# VentilationSystem_Rele.net
KiCad netlist of a schematic drawn in EAGLE
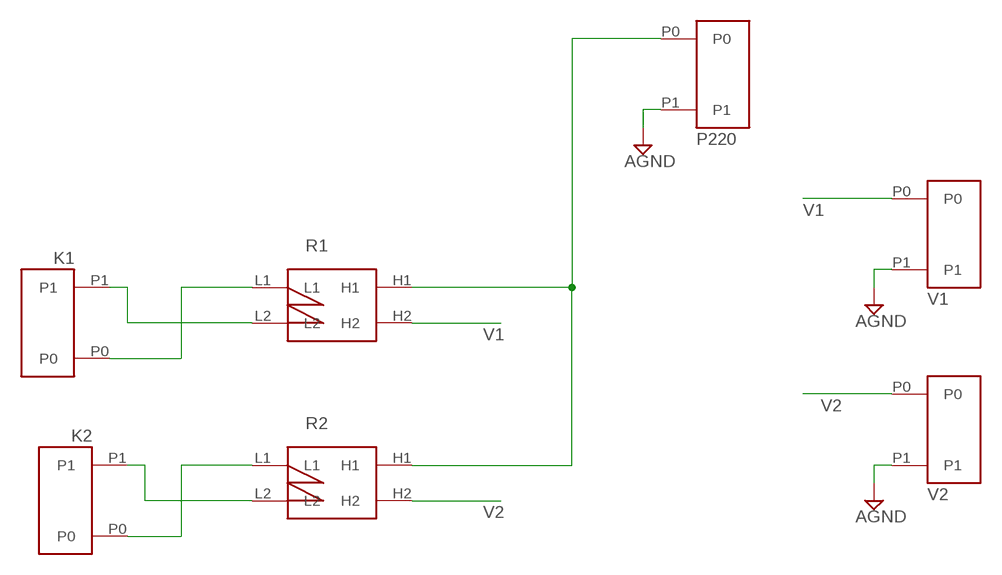
[diagram p0: schematic, sheet 1]

(export (version "E")
  (design (tool "Eeschema 10.0.6"))
  (components
    (comp (ref "K1")
      (value "RAIL_2")
      (footprint "eagle-import:RAIL_2")
      (libsource (lib "eagle-import") (part "RAIL_2"))
    )
    (comp (ref "K2")
      (value "RAIL_2")
      (footprint "eagle-import:RAIL_2")
      (libsource (lib "eagle-import") (part "RAIL_2"))
    )
    (comp (ref "P220")
      (value "RAIL_2")
      (footprint "eagle-import:RAIL_2")
      (libsource (lib "eagle-import") (part "RAIL_2"))
    )
    (comp (ref "R1")
      (value "NPR-RELE")
      (footprint "eagle-import:NPR-RELE")
      (libsource (lib "eagle-import") (part "NPR-RELE"))
    )
    (comp (ref "R2")
      (value "NPR-RELE")
      (footprint "eagle-import:NPR-RELE")
      (libsource (lib "eagle-import") (part "NPR-RELE"))
    )
    (comp (ref "V1")
      (value "RAIL_2")
      (footprint "eagle-import:RAIL_2")
      (libsource (lib "eagle-import") (part "RAIL_2"))
    )
    (comp (ref "V2")
      (value "RAIL_2")
      (footprint "eagle-import:RAIL_2")
      (libsource (lib "eagle-import") (part "RAIL_2"))
    )
  )
  (nets
    (net (code "1") (name "/V1") (class "Default")
      (node (ref "R1") (pin "H2") (pinfunction "H2_H2") (pintype "bidirectional"))
      (node (ref "V1") (pin "P0") (pinfunction "P0_P0") (pintype "bidirectional"))
    )
    (net (code "2") (name "/V2") (class "Default")
      (node (ref "R2") (pin "H2") (pinfunction "H2_H2") (pintype "bidirectional"))
      (node (ref "V2") (pin "P0") (pinfunction "P0_P0") (pintype "bidirectional"))
    )
    (net (code "3") (name "AGND") (class "Default")
      (node (ref "P220") (pin "P1") (pinfunction "P1_P1") (pintype "bidirectional"))
      (node (ref "V1") (pin "P1") (pinfunction "P1_P1") (pintype "bidirectional"))
      (node (ref "V2") (pin "P1") (pinfunction "P1_P1") (pintype "bidirectional"))
    )
    (net (code "4") (name "Net-(K1-PadP0)") (class "Default")
      (node (ref "K1") (pin "P0") (pinfunction "P0_P0") (pintype "bidirectional"))
      (node (ref "R1") (pin "L1") (pinfunction "L1_L1") (pintype "bidirectional"))
    )
    (net (code "5") (name "Net-(K1-PadP1)") (class "Default")
      (node (ref "K1") (pin "P1") (pinfunction "P1_P1") (pintype "bidirectional"))
      (node (ref "R1") (pin "L2") (pinfunction "L2_L2") (pintype "bidirectional"))
    )
    (net (code "6") (name "Net-(K2-PadP0)") (class "Default")
      (node (ref "K2") (pin "P0") (pinfunction "P0_P0") (pintype "bidirectional"))
      (node (ref "R2") (pin "L1") (pinfunction "L1_L1") (pintype "bidirectional"))
    )
    (net (code "7") (name "Net-(K2-PadP1)") (class "Default")
      (node (ref "K2") (pin "P1") (pinfunction "P1_P1") (pintype "bidirectional"))
      (node (ref "R2") (pin "L2") (pinfunction "L2_L2") (pintype "bidirectional"))
    )
    (net (code "8") (name "Net-(P220-PadP0)") (class "Default")
      (node (ref "P220") (pin "P0") (pinfunction "P0_P0") (pintype "bidirectional"))
      (node (ref "R1") (pin "H1") (pinfunction "H1_H1") (pintype "bidirectional"))
      (node (ref "R2") (pin "H1") (pinfunction "H1_H1") (pintype "bidirectional"))
    )
  )
)
